# YAPHITS.net
KiCad netlist of a schematic drawn in EAGLE
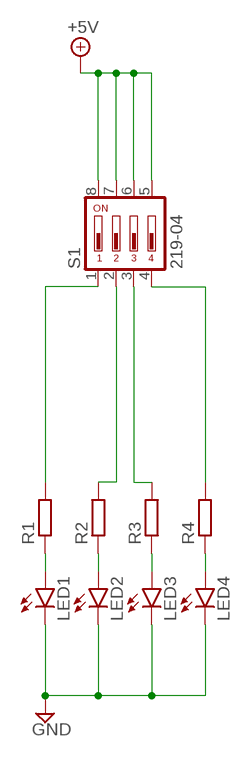
[diagram p0: schematic, sheet 1]

(export (version "E")
  (design (tool "Eeschema 10.0.6"))
  (components
    (comp (ref "LED1")
      (value "LAP4-BOTTOM")
      (footprint "eagle-import:P47F-BOTTOM")
      (libsource (lib "eagle-import") (part "P4-BOTTOMLA"))
    )
    (comp (ref "LED2")
      (value "LAP4-BOTTOM")
      (footprint "eagle-import:P47F-BOTTOM")
      (libsource (lib "eagle-import") (part "P4-BOTTOMLA"))
    )
    (comp (ref "LED3")
      (value "LAP4-BOTTOM")
      (footprint "eagle-import:P47F-BOTTOM")
      (libsource (lib "eagle-import") (part "P4-BOTTOMLA"))
    )
    (comp (ref "LED4")
      (value "LAP4-BOTTOM")
      (footprint "eagle-import:P47F-BOTTOM")
      (libsource (lib "eagle-import") (part "P4-BOTTOMLA"))
    )
    (comp (ref "R1")
      (value "R-EU_0204/7")
      (footprint "eagle-import:0204_7")
      (libsource (lib "eagle-import") (part "R-EU_0204/7"))
    )
    (comp (ref "R2")
      (value "R-EU_0204/7")
      (footprint "eagle-import:0204_7")
      (libsource (lib "eagle-import") (part "R-EU_0204/7"))
    )
    (comp (ref "R3")
      (value "R-EU_0204/7")
      (footprint "eagle-import:0204_7")
      (libsource (lib "eagle-import") (part "R-EU_0204/7"))
    )
    (comp (ref "R4")
      (value "R-EU_0204/7")
      (footprint "eagle-import:0204_7")
      (libsource (lib "eagle-import") (part "R-EU_0204/7"))
    )
    (comp (ref "S1")
      (value "219-04")
      (footprint "eagle-import:CTS-219-04")
      (libsource (lib "eagle-import") (part "219-04"))
    )
  )
  (nets
    (net (code "1") (name "+5V") (class "Default")
      (node (ref "S1") (pin "5") (pinfunction "5_5") (pintype "passive"))
      (node (ref "S1") (pin "6") (pinfunction "6_6") (pintype "passive"))
      (node (ref "S1") (pin "7") (pinfunction "7_7") (pintype "passive"))
      (node (ref "S1") (pin "8") (pinfunction "8_8") (pintype "passive"))
    )
    (net (code "2") (name "GND") (class "Default")
      (node (ref "LED1") (pin "C") (pinfunction "C_C") (pintype "passive"))
      (node (ref "LED2") (pin "C") (pinfunction "C_C") (pintype "passive"))
      (node (ref "LED3") (pin "C") (pinfunction "C_C") (pintype "passive"))
      (node (ref "LED4") (pin "C") (pinfunction "C_C") (pintype "passive"))
    )
    (net (code "3") (name "Net-(LED1-PadA)") (class "Default")
      (node (ref "LED1") (pin "A") (pinfunction "A_A") (pintype "passive"))
      (node (ref "R1") (pin "1") (pinfunction "1_1") (pintype "passive"))
    )
    (net (code "4") (name "Net-(LED2-PadA)") (class "Default")
      (node (ref "LED2") (pin "A") (pinfunction "A_A") (pintype "passive"))
      (node (ref "R2") (pin "1") (pinfunction "1_1") (pintype "passive"))
    )
    (net (code "5") (name "Net-(LED3-PadA)") (class "Default")
      (node (ref "LED3") (pin "A") (pinfunction "A_A") (pintype "passive"))
      (node (ref "R3") (pin "1") (pinfunction "1_1") (pintype "passive"))
    )
    (net (code "6") (name "Net-(LED4-PadA)") (class "Default")
      (node (ref "LED4") (pin "A") (pinfunction "A_A") (pintype "passive"))
      (node (ref "R4") (pin "1") (pinfunction "1_1") (pintype "passive"))
    )
    (net (code "7") (name "Net-(R1-Pad2)") (class "Default")
      (node (ref "R1") (pin "2") (pinfunction "2_2") (pintype "passive"))
      (node (ref "S1") (pin "1") (pinfunction "1_1") (pintype "passive"))
    )
    (net (code "8") (name "Net-(R2-Pad2)") (class "Default")
      (node (ref "R2") (pin "2") (pinfunction "2_2") (pintype "passive"))
      (node (ref "S1") (pin "2") (pinfunction "2_2") (pintype "passive"))
    )
    (net (code "9") (name "Net-(R3-Pad2)") (class "Default")
      (node (ref "R3") (pin "2") (pinfunction "2_2") (pintype "passive"))
      (node (ref "S1") (pin "3") (pinfunction "3_3") (pintype "passive"))
    )
    (net (code "10") (name "Net-(R4-Pad2)") (class "Default")
      (node (ref "R4") (pin "2") (pinfunction "2_2") (pintype "passive"))
      (node (ref "S1") (pin "4") (pinfunction "4_4") (pintype "passive"))
    )
  )
)
